# midi-in-out-micro.net
KiCad netlist of a schematic drawn in EAGLE
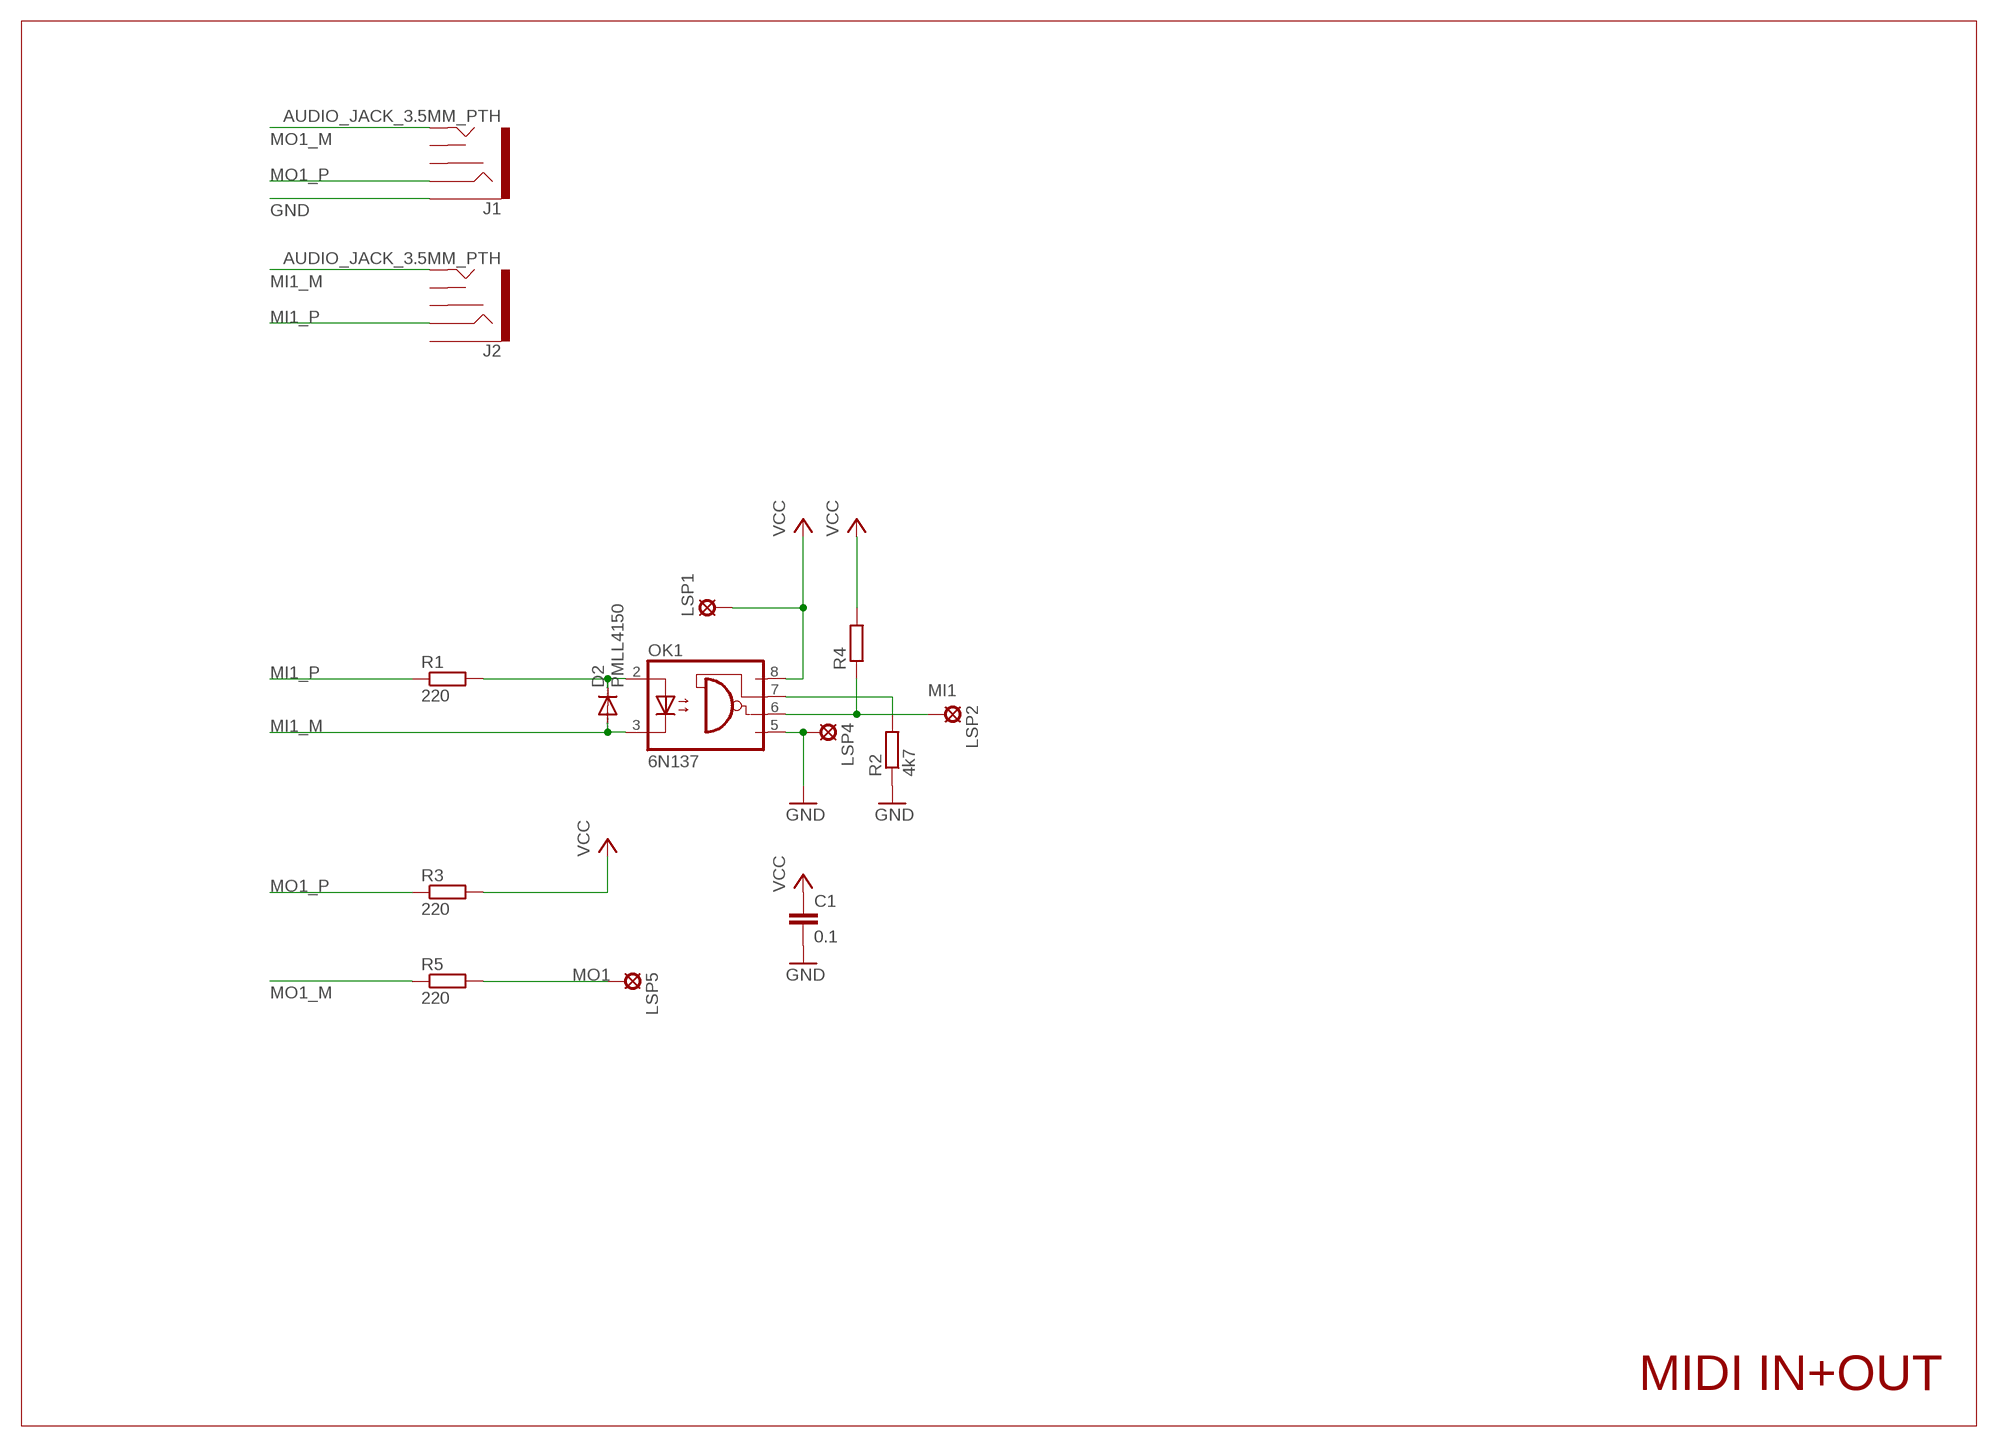
[diagram p0: schematic, sheet 1]

(export (version "E")
  (design (tool "Eeschema 10.0.6"))
  (components
    (comp (ref "C1")
      (value "0.1")
      (footprint "eagle-import:C0805")
      (libsource (lib "eagle-import") (part "C-EUC0805"))
    )
    (comp (ref "D2")
      (value "PMLL4150")
      (footprint "eagle-import:SOD80C")
      (libsource (lib "eagle-import") (part "PMLL4150"))
    )
    (comp (ref "J1")
      (value "AUDIO_JACK_3.5MM_PTH")
      (footprint "eagle-import:AUDIO-JACK")
      (libsource (lib "eagle-import") (part "AUDIO_JACK_3.5MM_PTH"))
    )
    (comp (ref "J2")
      (value "AUDIO_JACK_3.5MM_PTH")
      (footprint "eagle-import:AUDIO-JACK")
      (libsource (lib "eagle-import") (part "AUDIO_JACK_3.5MM_PTH"))
    )
    (comp (ref "LSP1")
      (value "MCS10B")
      (footprint "eagle-import:MCS10B")
      (libsource (lib "eagle-import") (part "MCS10B"))
    )
    (comp (ref "LSP2")
      (value "MCS10B")
      (footprint "eagle-import:MCS10B")
      (libsource (lib "eagle-import") (part "MCS10B"))
    )
    (comp (ref "LSP4")
      (value "MCS10B")
      (footprint "eagle-import:MCS10B")
      (libsource (lib "eagle-import") (part "MCS10B"))
    )
    (comp (ref "LSP5")
      (value "MCS10B")
      (footprint "eagle-import:MCS10B")
      (libsource (lib "eagle-import") (part "MCS10B"))
    )
    (comp (ref "OK1")
      (value "6N137")
      (footprint "eagle-import:DIL08")
      (libsource (lib "eagle-import") (part "6N137"))
    )
    (comp (ref "R1")
      (value "220")
      (footprint "eagle-import:R0805")
      (libsource (lib "eagle-import") (part "R-EU_R0805"))
    )
    (comp (ref "R2")
      (value "4k7")
      (footprint "eagle-import:R0805")
      (libsource (lib "eagle-import") (part "R-EU_R0805"))
    )
    (comp (ref "R3")
      (value "220")
      (footprint "eagle-import:R0805")
      (libsource (lib "eagle-import") (part "R-EU_R0805"))
    )
    (comp (ref "R4")
      (value "R-EU_0207/5V")
      (footprint "eagle-import:0207_5V")
      (libsource (lib "eagle-import") (part "R-EU_0207/5V"))
    )
    (comp (ref "R5")
      (value "220")
      (footprint "eagle-import:R0805")
      (libsource (lib "eagle-import") (part "R-EU_R0805"))
    )
  )
  (nets
    (net (code "1") (name "/MI1") (class "Default")
      (node (ref "LSP2") (pin "MP") (pinfunction "MP_MP") (pintype "passive"))
      (node (ref "OK1") (pin "6") (pinfunction "VO_6") (pintype "passive"))
      (node (ref "R4") (pin "1") (pinfunction "1_1") (pintype "passive"))
    )
    (net (code "2") (name "/MI1_M") (class "Default")
      (node (ref "D2") (pin "A") (pinfunction "A_A") (pintype "passive"))
      (node (ref "J2") (pin "TIP") (pinfunction "TIP_TIP") (pintype "bidirectional"))
      (node (ref "OK1") (pin "3") (pinfunction "C_3") (pintype "passive"))
    )
    (net (code "3") (name "/MI1_P") (class "Default")
      (node (ref "J2") (pin "RING") (pinfunction "RING_RING") (pintype "bidirectional"))
      (node (ref "R1") (pin "1") (pinfunction "1_1") (pintype "passive"))
    )
    (net (code "4") (name "/MO1") (class "Default")
      (node (ref "LSP5") (pin "MP") (pinfunction "MP_MP") (pintype "passive"))
      (node (ref "R5") (pin "2") (pinfunction "2_2") (pintype "passive"))
    )
    (net (code "5") (name "/MO1_M") (class "Default")
      (node (ref "J1") (pin "TIP") (pinfunction "TIP_TIP") (pintype "bidirectional"))
      (node (ref "R5") (pin "1") (pinfunction "1_1") (pintype "passive"))
    )
    (net (code "6") (name "/MO1_P") (class "Default")
      (node (ref "J1") (pin "RING") (pinfunction "RING_RING") (pintype "bidirectional"))
      (node (ref "R3") (pin "1") (pinfunction "1_1") (pintype "passive"))
    )
    (net (code "7") (name "GND") (class "Default")
      (node (ref "C1") (pin "2") (pinfunction "2_2") (pintype "passive"))
      (node (ref "J1") (pin "SLEEVE") (pinfunction "SLEEVE_SLEEVE") (pintype "bidirectional"))
      (node (ref "LSP4") (pin "MP") (pinfunction "MP_MP") (pintype "passive"))
      (node (ref "OK1") (pin "5") (pinfunction "GND_5") (pintype "passive"))
      (node (ref "R2") (pin "1") (pinfunction "1_1") (pintype "passive"))
    )
    (net (code "8") (name "Net-(OK1-A)") (class "Default")
      (node (ref "D2") (pin "C") (pinfunction "C_C") (pintype "passive"))
      (node (ref "OK1") (pin "2") (pinfunction "A_2") (pintype "passive"))
      (node (ref "R1") (pin "2") (pinfunction "2_2") (pintype "passive"))
    )
    (net (code "9") (name "Net-(OK1-VE)") (class "Default")
      (node (ref "OK1") (pin "7") (pinfunction "VE_7") (pintype "passive"))
      (node (ref "R2") (pin "2") (pinfunction "2_2") (pintype "passive"))
    )
    (net (code "10") (name "VCC") (class "Default")
      (node (ref "C1") (pin "1") (pinfunction "1_1") (pintype "passive"))
      (node (ref "LSP1") (pin "MP") (pinfunction "MP_MP") (pintype "passive"))
      (node (ref "OK1") (pin "8") (pinfunction "VCC_8") (pintype "passive"))
      (node (ref "R3") (pin "2") (pinfunction "2_2") (pintype "passive"))
      (node (ref "R4") (pin "2") (pinfunction "2_2") (pintype "passive"))
    )
    (net (code "11") (name "unconnected-(J1-PadRSH)") (class "Default")
      (node (ref "J1") (pin "RSH") (pinfunction "RSH_RSH") (pintype "bidirectional"))
    )
    (net (code "12") (name "unconnected-(J1-PadTSH)") (class "Default")
      (node (ref "J1") (pin "TSH") (pinfunction "TSH_TSH") (pintype "bidirectional"))
    )
    (net (code "13") (name "unconnected-(J2-PadRSH)") (class "Default")
      (node (ref "J2") (pin "RSH") (pinfunction "RSH_RSH") (pintype "bidirectional"))
    )
    (net (code "14") (name "unconnected-(J2-PadSLEEVE)") (class "Default")
      (node (ref "J2") (pin "SLEEVE") (pinfunction "SLEEVE_SLEEVE") (pintype "bidirectional"))
    )
    (net (code "15") (name "unconnected-(J2-PadTSH)") (class "Default")
      (node (ref "J2") (pin "TSH") (pinfunction "TSH_TSH") (pintype "bidirectional"))
    )
  )
)
